# LazuriteMiniDongle3.net
KiCad netlist of a schematic drawn in EAGLE
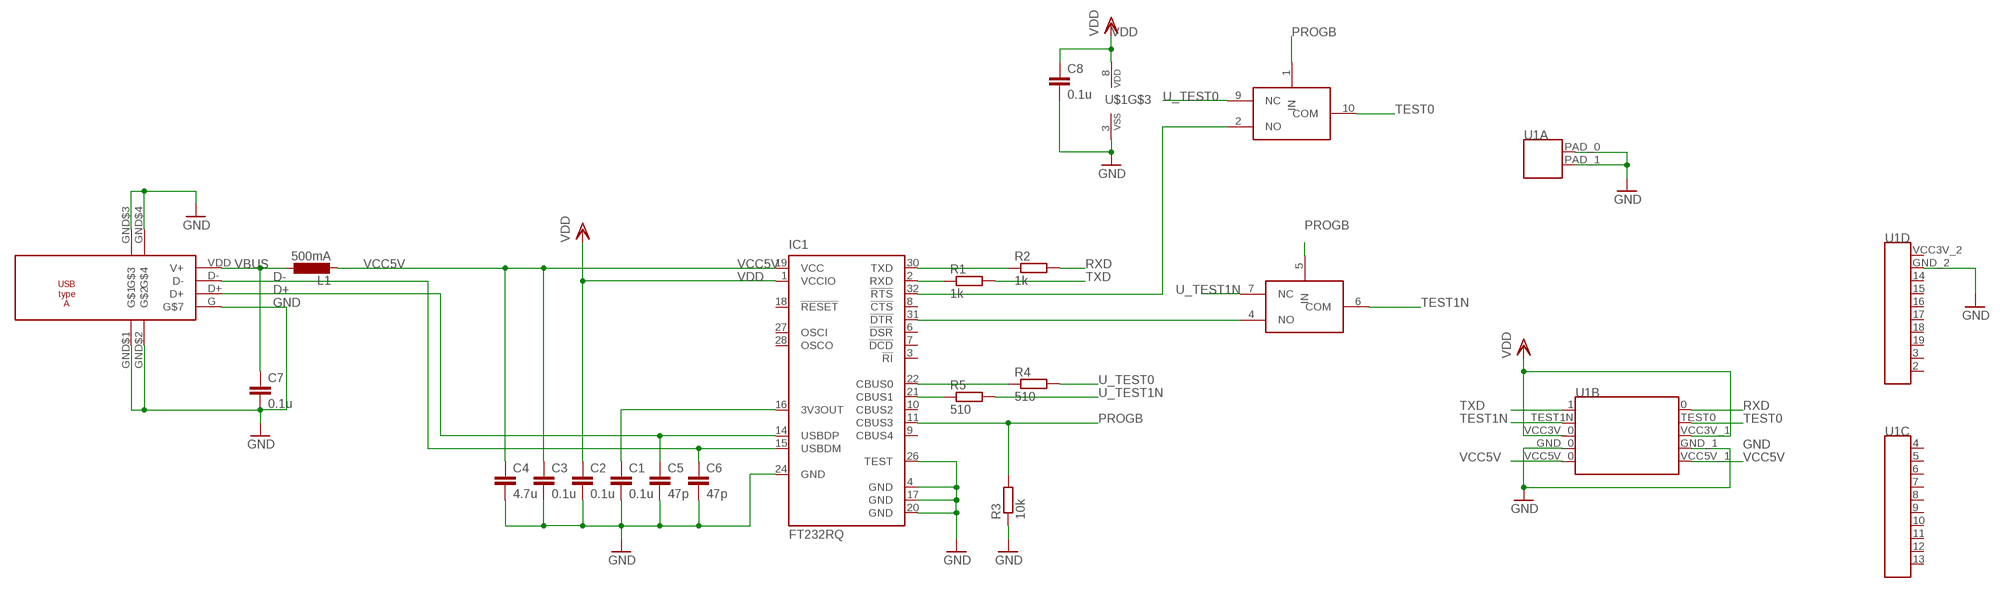
[diagram p0: schematic, sheet 1]

(export (version "E")
  (design (tool "Eeschema 10.0.6"))
  (components
    (comp (ref "C1")
      (value "0.1u")
      (footprint "eagle-import:C0402")
      (libsource (lib "eagle-import") (part "C-EUC0402"))
    )
    (comp (ref "C2")
      (value "0.1u")
      (footprint "eagle-import:C0402")
      (libsource (lib "eagle-import") (part "C-EUC0402"))
    )
    (comp (ref "C3")
      (value "0.1u")
      (footprint "eagle-import:C0402")
      (libsource (lib "eagle-import") (part "C-EUC0402"))
    )
    (comp (ref "C4")
      (value "4.7u")
      (footprint "eagle-import:C1608")
      (libsource (lib "eagle-import") (part "resistor_C-EUC1608"))
    )
    (comp (ref "C5")
      (value "47p")
      (footprint "eagle-import:C0402")
      (libsource (lib "eagle-import") (part "C-EUC0402"))
    )
    (comp (ref "C6")
      (value "47p")
      (footprint "eagle-import:C0402")
      (libsource (lib "eagle-import") (part "C-EUC0402"))
    )
    (comp (ref "C7")
      (value "0.1u")
      (footprint "eagle-import:C0402")
      (libsource (lib "eagle-import") (part "C-EUC0402"))
    )
    (comp (ref "C8")
      (value "0.1u")
      (footprint "eagle-import:C0402")
      (libsource (lib "eagle-import") (part "C-EUC0402"))
    )
    (comp (ref "IC1")
      (value "FT232RQ")
      (footprint "eagle-import:QFN32")
      (libsource (lib "eagle-import") (part "FT232RQ"))
    )
    (comp (ref "L1")
      (value "500mA")
      (footprint "eagle-import:L1812")
      (libsource (lib "eagle-import") (part "L-EUL1812"))
    )
    (comp (ref "R1")
      (value "1k")
      (footprint "eagle-import:R0402")
      (libsource (lib "eagle-import") (part "R-EU_R0402"))
    )
    (comp (ref "R2")
      (value "1k")
      (footprint "eagle-import:R0402")
      (libsource (lib "eagle-import") (part "R-EU_R0402"))
    )
    (comp (ref "R3")
      (value "10k")
      (footprint "eagle-import:R0402")
      (libsource (lib "eagle-import") (part "R-EU_R0402"))
    )
    (comp (ref "R4")
      (value "510")
      (footprint "eagle-import:R0402")
      (libsource (lib "eagle-import") (part "R-EU_R0402"))
    )
    (comp (ref "R5")
      (value "510")
      (footprint "eagle-import:R0402")
      (libsource (lib "eagle-import") (part "R-EU_R0402"))
    )
    (comp (ref "U$1")
      (value "TI-TS5A23159")
      (footprint "eagle-import:UQFN10")
      (libsource (lib "eagle-import") (part "TI-TS5A23159"))
    )
    (comp (ref "U$2")
      (value "USB-TYPE-A")
      (footprint "eagle-import:UP2-AH-TH")
      (libsource (lib "eagle-import") (part "USB-TYPE-A"))
    )
    (comp (ref "U1")
      (value "LAZURITE920JLAZURITE920J")
      (footprint "eagle-import:LAZURITE920J")
      (libsource (lib "eagle-import") (part "LAZURITE920JLAZURITE920J"))
    )
  )
  (nets
    (net (code "1") (name "/D+") (class "Default")
      (node (ref "C5") (pin "1") (pinfunction "1_1") (pintype "passive"))
      (node (ref "IC1") (pin "14") (pinfunction "USBDP_14") (pintype "bidirectional"))
      (node (ref "U$2") (pin "D+") (pinfunction "D+_D+") (pintype "bidirectional"))
    )
    (net (code "2") (name "/D-") (class "Default")
      (node (ref "C6") (pin "1") (pinfunction "1_1") (pintype "passive"))
      (node (ref "IC1") (pin "15") (pinfunction "USBDM_15") (pintype "bidirectional"))
      (node (ref "U$2") (pin "D-") (pinfunction "D-_D-") (pintype "bidirectional"))
    )
    (net (code "3") (name "/PROGB") (class "Default")
      (node (ref "IC1") (pin "11") (pinfunction "CBUS3_11") (pintype "bidirectional"))
      (node (ref "R3") (pin "2") (pinfunction "2_2") (pintype "passive"))
      (node (ref "U$1") (pin "1") (pinfunction "IN_1") (pintype "bidirectional"))
      (node (ref "U$1") (pin "5") (pinfunction "IN_5") (pintype "bidirectional"))
    )
    (net (code "4") (name "/RXD") (class "Default")
      (node (ref "R2") (pin "2") (pinfunction "2_2") (pintype "passive"))
      (node (ref "U1") (pin "0") (pinfunction "0_0") (pintype "passive"))
    )
    (net (code "5") (name "/TEST0") (class "Default")
      (node (ref "U$1") (pin "10") (pinfunction "COM_10") (pintype "bidirectional"))
      (node (ref "U1") (pin "TEST0") (pinfunction "TEST0_TEST0") (pintype "passive"))
    )
    (net (code "6") (name "/TEST1N") (class "Default")
      (node (ref "U$1") (pin "6") (pinfunction "COM_6") (pintype "bidirectional"))
      (node (ref "U1") (pin "TEST1N") (pinfunction "TEST1N_TEST1N") (pintype "passive"))
    )
    (net (code "7") (name "/TXD") (class "Default")
      (node (ref "R1") (pin "2") (pinfunction "2_2") (pintype "passive"))
      (node (ref "U1") (pin "1") (pinfunction "1_1") (pintype "passive"))
    )
    (net (code "8") (name "/U_TEST0") (class "Default")
      (node (ref "R4") (pin "2") (pinfunction "2_2") (pintype "passive"))
      (node (ref "U$1") (pin "9") (pinfunction "NC_9") (pintype "bidirectional"))
    )
    (net (code "9") (name "/U_TEST1N") (class "Default")
      (node (ref "R5") (pin "2") (pinfunction "2_2") (pintype "passive"))
      (node (ref "U$1") (pin "7") (pinfunction "NC_7") (pintype "bidirectional"))
    )
    (net (code "10") (name "/VBUS") (class "Default")
      (node (ref "C7") (pin "1") (pinfunction "1_1") (pintype "passive"))
      (node (ref "L1") (pin "1") (pinfunction "1_1") (pintype "passive"))
      (node (ref "U$2") (pin "VDD") (pinfunction "V+_VDD") (pintype "bidirectional"))
    )
    (net (code "11") (name "/VCC5V") (class "Default")
      (node (ref "C3") (pin "1") (pinfunction "1_1") (pintype "passive"))
      (node (ref "C4") (pin "1") (pinfunction "1_1") (pintype "passive"))
      (node (ref "IC1") (pin "19") (pinfunction "VCC_19") (pintype "power_in"))
      (node (ref "L1") (pin "2") (pinfunction "2_2") (pintype "passive"))
      (node (ref "U1") (pin "VCC5V_0") (pinfunction "VCC5V_0_VCC5V_0") (pintype "passive"))
      (node (ref "U1") (pin "VCC5V_1") (pinfunction "VCC5V_1_VCC5V_1") (pintype "passive"))
    )
    (net (code "12") (name "GND") (class "Default")
      (node (ref "C1") (pin "2") (pinfunction "2_2") (pintype "passive"))
      (node (ref "C2") (pin "2") (pinfunction "2_2") (pintype "passive"))
      (node (ref "C3") (pin "2") (pinfunction "2_2") (pintype "passive"))
      (node (ref "C4") (pin "2") (pinfunction "2_2") (pintype "passive"))
      (node (ref "C5") (pin "2") (pinfunction "2_2") (pintype "passive"))
      (node (ref "C6") (pin "2") (pinfunction "2_2") (pintype "passive"))
      (node (ref "C7") (pin "2") (pinfunction "2_2") (pintype "passive"))
      (node (ref "C8") (pin "2") (pinfunction "2_2") (pintype "passive"))
      (node (ref "IC1") (pin "17") (pinfunction "GND_17") (pintype "power_in"))
      (node (ref "IC1") (pin "20") (pinfunction "GND_20") (pintype "power_in"))
      (node (ref "IC1") (pin "24") (pinfunction "GND_24") (pintype "power_in"))
      (node (ref "IC1") (pin "26") (pinfunction "TEST_26") (pintype "input"))
      (node (ref "IC1") (pin "4") (pinfunction "GND_4") (pintype "power_in"))
      (node (ref "R3") (pin "1") (pinfunction "1_1") (pintype "passive"))
      (node (ref "U$1") (pin "3") (pinfunction "VSS_3") (pintype "power_in"))
      (node (ref "U$2") (pin "G") (pinfunction "G$7_G") (pintype "power_in"))
      (node (ref "U$2") (pin "GND$1") (pinfunction "G$1_GND$1") (pintype "power_in"))
      (node (ref "U$2") (pin "GND$2") (pinfunction "G$2_GND$2") (pintype "power_in"))
      (node (ref "U$2") (pin "GND$3") (pinfunction "G$3_GND$3") (pintype "power_in"))
      (node (ref "U$2") (pin "GND$4") (pinfunction "G$4_GND$4") (pintype "power_in"))
      (node (ref "U1") (pin "GND_0") (pinfunction "GND_0_GND_0") (pintype "passive"))
      (node (ref "U1") (pin "GND_1") (pinfunction "GND_1_GND_1") (pintype "passive"))
      (node (ref "U1") (pin "GND_2") (pinfunction "GND_2_GND_2") (pintype "passive"))
      (node (ref "U1") (pin "PAD_0") (pinfunction "PAD_0_PAD_0") (pintype "passive"))
      (node (ref "U1") (pin "PAD_1") (pinfunction "PAD_1_PAD_1") (pintype "passive"))
    )
    (net (code "13") (name "Net-(IC1-3V3OUT)") (class "Default")
      (node (ref "C1") (pin "1") (pinfunction "1_1") (pintype "passive"))
      (node (ref "IC1") (pin "16") (pinfunction "3V3OUT_16") (pintype "output"))
    )
    (net (code "14") (name "Net-(IC1-CBUS0)") (class "Default")
      (node (ref "IC1") (pin "22") (pinfunction "CBUS0_22") (pintype "bidirectional"))
      (node (ref "R4") (pin "1") (pinfunction "1_1") (pintype "passive"))
    )
    (net (code "15") (name "Net-(IC1-CBUS1)") (class "Default")
      (node (ref "IC1") (pin "21") (pinfunction "CBUS1_21") (pintype "bidirectional"))
      (node (ref "R5") (pin "1") (pinfunction "1_1") (pintype "passive"))
    )
    (net (code "16") (name "Net-(IC1-RXD)") (class "Default")
      (node (ref "IC1") (pin "2") (pinfunction "RXD_2") (pintype "input"))
      (node (ref "R1") (pin "1") (pinfunction "1_1") (pintype "passive"))
    )
    (net (code "17") (name "Net-(IC1-TXD)") (class "Default")
      (node (ref "IC1") (pin "30") (pinfunction "TXD_30") (pintype "output"))
      (node (ref "R2") (pin "1") (pinfunction "1_1") (pintype "passive"))
    )
    (net (code "18") (name "Net-(IC1-~{DTR})") (class "Default")
      (node (ref "IC1") (pin "31") (pinfunction "~{DTR}_31") (pintype "output"))
      (node (ref "U$1") (pin "4") (pinfunction "NO_4") (pintype "bidirectional"))
    )
    (net (code "19") (name "Net-(IC1-~{RTS})") (class "Default")
      (node (ref "IC1") (pin "32") (pinfunction "~{RTS}_32") (pintype "output"))
      (node (ref "U$1") (pin "2") (pinfunction "NO_2") (pintype "bidirectional"))
    )
    (net (code "20") (name "VDD") (class "Default")
      (node (ref "C2") (pin "1") (pinfunction "1_1") (pintype "passive"))
      (node (ref "C8") (pin "1") (pinfunction "1_1") (pintype "passive"))
      (node (ref "IC1") (pin "1") (pinfunction "VCCIO_1") (pintype "power_in"))
      (node (ref "U$1") (pin "8") (pinfunction "VDD_8") (pintype "power_in"))
      (node (ref "U1") (pin "VCC3V_0") (pinfunction "VCC3V_0_VCC3V_0") (pintype "passive"))
      (node (ref "U1") (pin "VCC3V_1") (pinfunction "VCC3V_1_VCC3V_1") (pintype "passive"))
    )
    (net (code "21") (name "unconnected-(IC1-CBUS2-Pad10)") (class "Default")
      (node (ref "IC1") (pin "10") (pinfunction "CBUS2_10") (pintype "bidirectional"))
    )
    (net (code "22") (name "unconnected-(IC1-CBUS4-Pad9)") (class "Default")
      (node (ref "IC1") (pin "9") (pinfunction "CBUS4_9") (pintype "bidirectional"))
    )
    (net (code "23") (name "unconnected-(IC1-OSCI-Pad27)") (class "Default")
      (node (ref "IC1") (pin "27") (pinfunction "OSCI_27") (pintype "input"))
    )
    (net (code "24") (name "unconnected-(IC1-OSCO-Pad28)") (class "Default")
      (node (ref "IC1") (pin "28") (pinfunction "OSCO_28") (pintype "output"))
    )
    (net (code "25") (name "unconnected-(IC1-~{CTS}-Pad8)") (class "Default")
      (node (ref "IC1") (pin "8") (pinfunction "~{CTS}_8") (pintype "input"))
    )
    (net (code "26") (name "unconnected-(IC1-~{DCD}-Pad7)") (class "Default")
      (node (ref "IC1") (pin "7") (pinfunction "~{DCD}_7") (pintype "input"))
    )
    (net (code "27") (name "unconnected-(IC1-~{DSR}-Pad6)") (class "Default")
      (node (ref "IC1") (pin "6") (pinfunction "~{DSR}_6") (pintype "input"))
    )
    (net (code "28") (name "unconnected-(IC1-~{RESET}-Pad18)") (class "Default")
      (node (ref "IC1") (pin "18") (pinfunction "~{RESET}_18") (pintype "input"))
    )
    (net (code "29") (name "unconnected-(IC1-~{RI}-Pad3)") (class "Default")
      (node (ref "IC1") (pin "3") (pinfunction "~{RI}_3") (pintype "input"))
    )
    (net (code "30") (name "unconnected-(U1-Pad2)") (class "Default")
      (node (ref "U1") (pin "2") (pinfunction "2_2") (pintype "passive"))
    )
    (net (code "31") (name "unconnected-(U1-Pad3)") (class "Default")
      (node (ref "U1") (pin "3") (pinfunction "3_3") (pintype "passive"))
    )
    (net (code "32") (name "unconnected-(U1-Pad4)") (class "Default")
      (node (ref "U1") (pin "4") (pinfunction "4_4") (pintype "passive"))
    )
    (net (code "33") (name "unconnected-(U1-Pad5)") (class "Default")
      (node (ref "U1") (pin "5") (pinfunction "5_5") (pintype "passive"))
    )
    (net (code "34") (name "unconnected-(U1-Pad6)") (class "Default")
      (node (ref "U1") (pin "6") (pinfunction "6_6") (pintype "passive"))
    )
    (net (code "35") (name "unconnected-(U1-Pad7)") (class "Default")
      (node (ref "U1") (pin "7") (pinfunction "7_7") (pintype "passive"))
    )
    (net (code "36") (name "unconnected-(U1-Pad8)") (class "Default")
      (node (ref "U1") (pin "8") (pinfunction "8_8") (pintype "passive"))
    )
    (net (code "37") (name "unconnected-(U1-Pad9)") (class "Default")
      (node (ref "U1") (pin "9") (pinfunction "9_9") (pintype "passive"))
    )
    (net (code "38") (name "unconnected-(U1-Pad10)") (class "Default")
      (node (ref "U1") (pin "10") (pinfunction "10_10") (pintype "passive"))
    )
    (net (code "39") (name "unconnected-(U1-Pad11)") (class "Default")
      (node (ref "U1") (pin "11") (pinfunction "11_11") (pintype "passive"))
    )
    (net (code "40") (name "unconnected-(U1-Pad12)") (class "Default")
      (node (ref "U1") (pin "12") (pinfunction "12_12") (pintype "passive"))
    )
    (net (code "41") (name "unconnected-(U1-Pad13)") (class "Default")
      (node (ref "U1") (pin "13") (pinfunction "13_13") (pintype "passive"))
    )
    (net (code "42") (name "unconnected-(U1-Pad14)") (class "Default")
      (node (ref "U1") (pin "14") (pinfunction "14_14") (pintype "passive"))
    )
    (net (code "43") (name "unconnected-(U1-Pad15)") (class "Default")
      (node (ref "U1") (pin "15") (pinfunction "15_15") (pintype "passive"))
    )
    (net (code "44") (name "unconnected-(U1-Pad16)") (class "Default")
      (node (ref "U1") (pin "16") (pinfunction "16_16") (pintype "passive"))
    )
    (net (code "45") (name "unconnected-(U1-Pad17)") (class "Default")
      (node (ref "U1") (pin "17") (pinfunction "17_17") (pintype "passive"))
    )
    (net (code "46") (name "unconnected-(U1-Pad18)") (class "Default")
      (node (ref "U1") (pin "18") (pinfunction "18_18") (pintype "passive"))
    )
    (net (code "47") (name "unconnected-(U1-Pad19)") (class "Default")
      (node (ref "U1") (pin "19") (pinfunction "19_19") (pintype "passive"))
    )
    (net (code "48") (name "unconnected-(U1-PadVCC3V_2)") (class "Default")
      (node (ref "U1") (pin "VCC3V_2") (pinfunction "VCC3V_2_VCC3V_2") (pintype "passive"))
    )
  )
)
